# obc-v2_POWER.net
KiCad netlist of a schematic drawn in Altium Designer
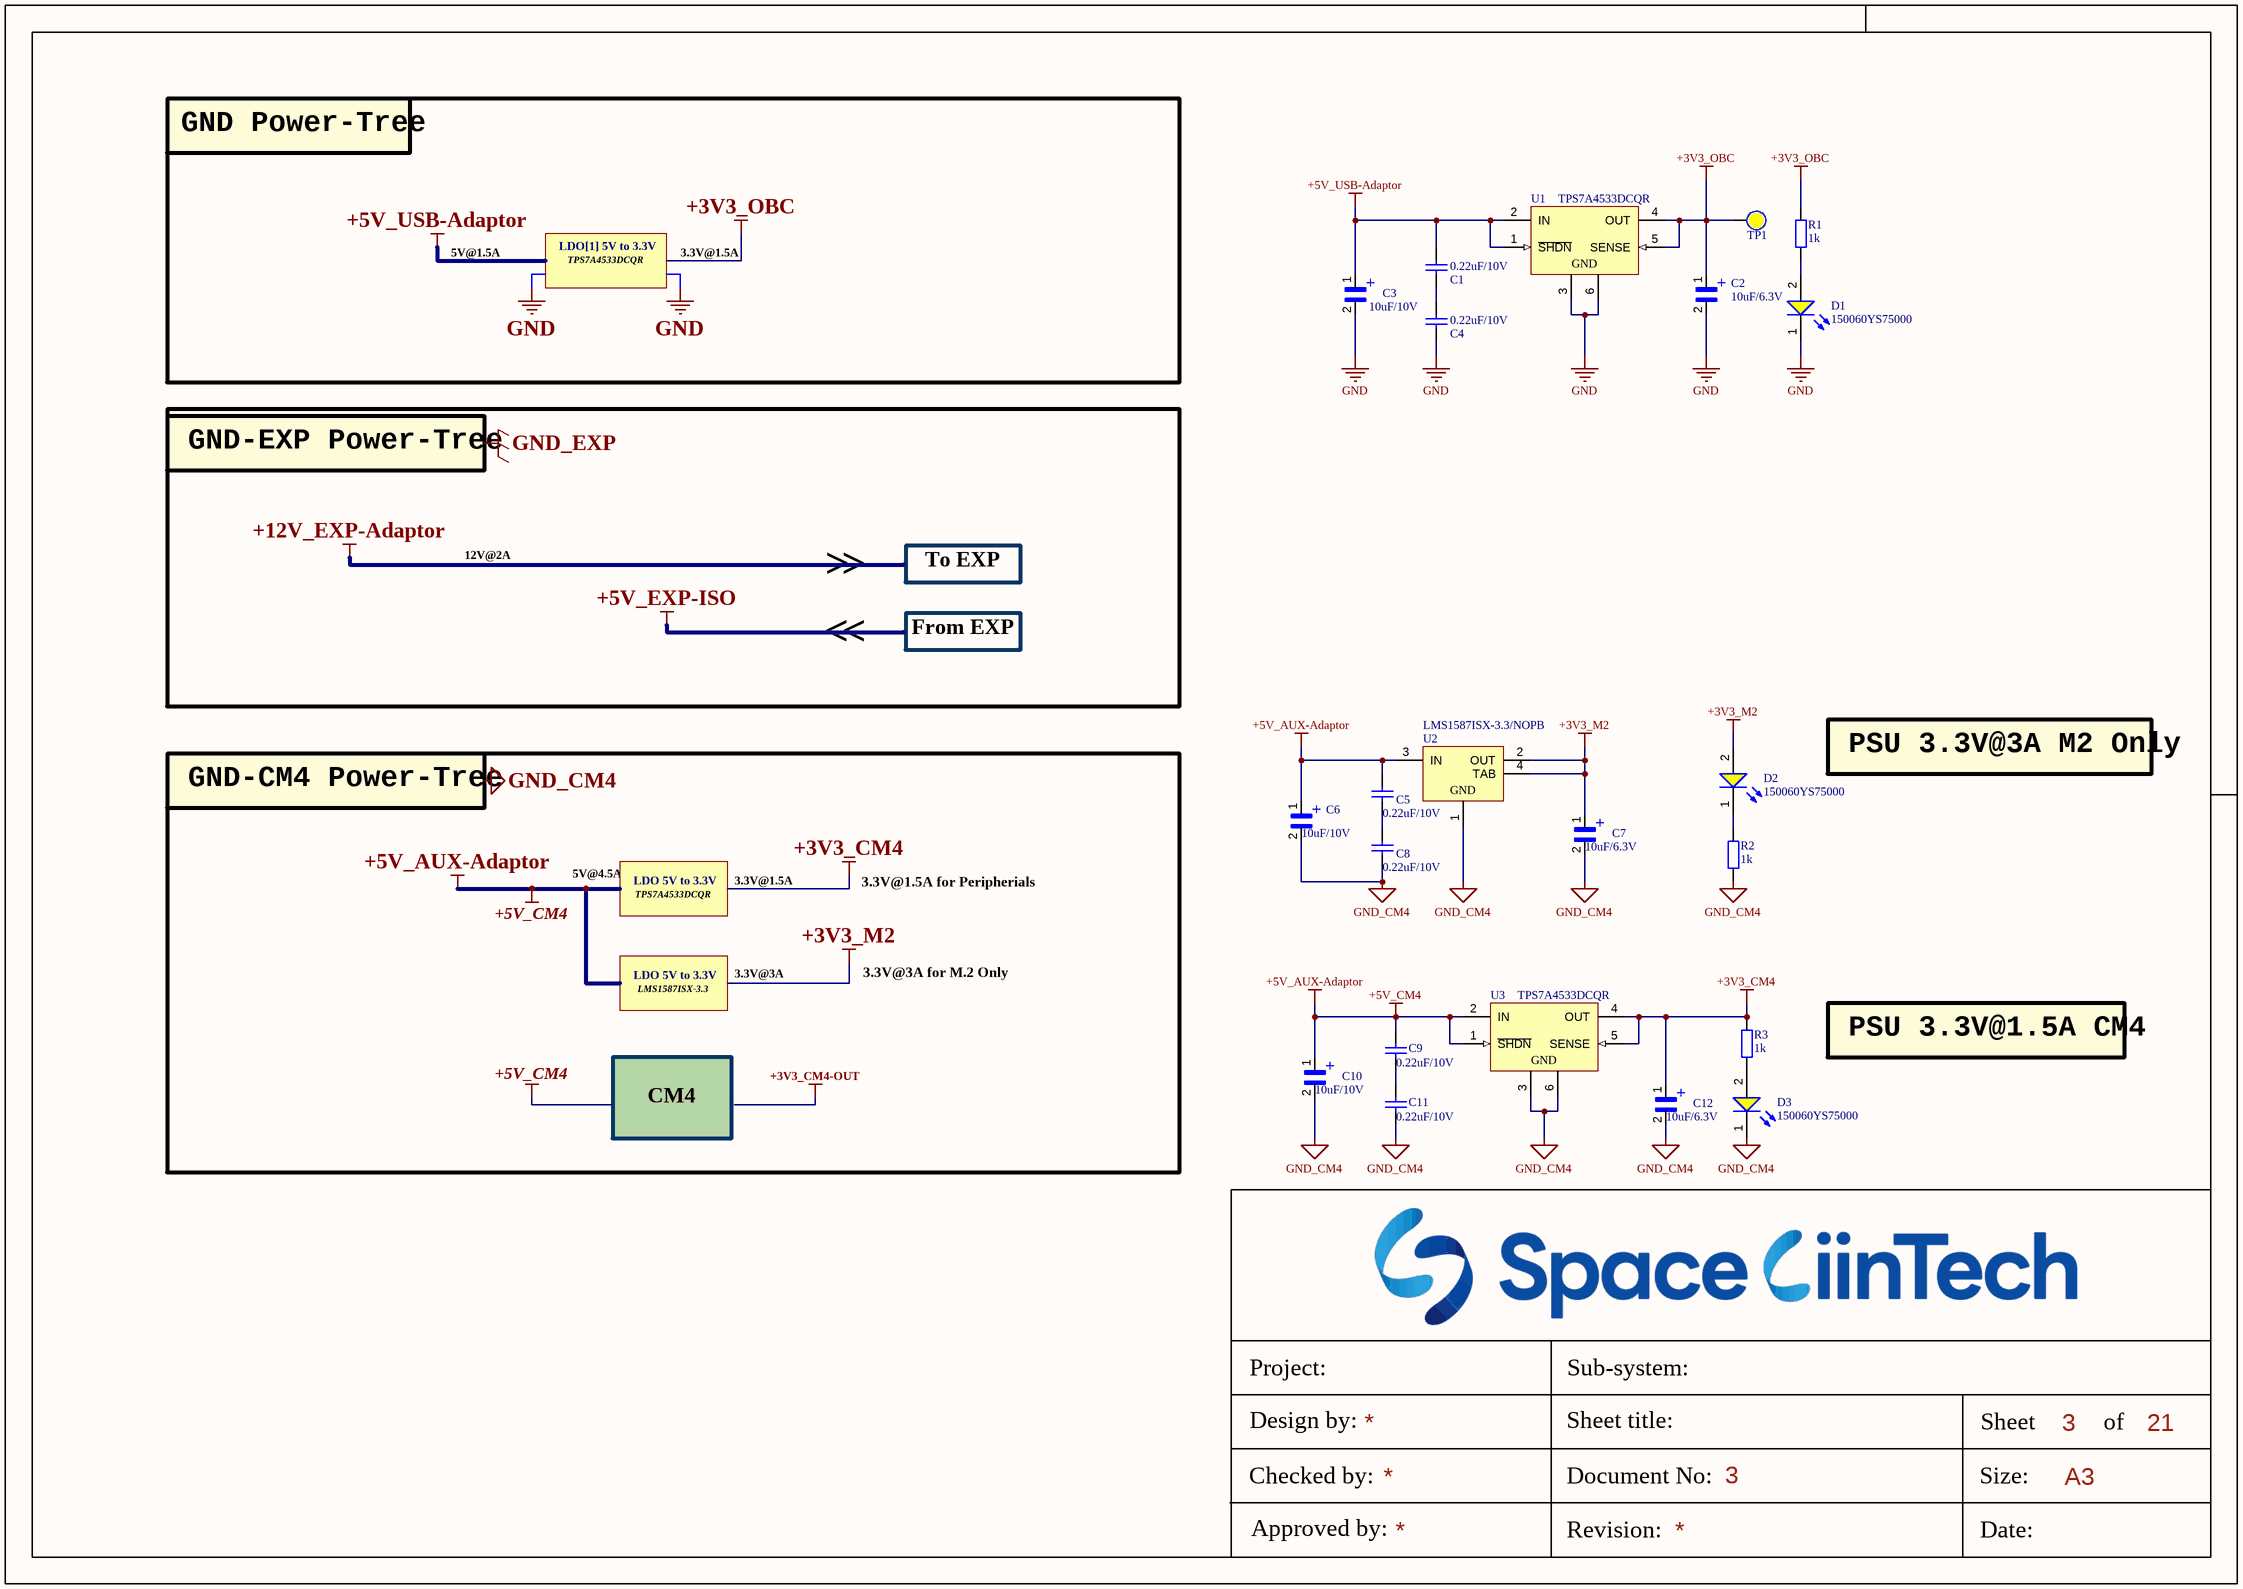
[diagram p0: obc-v2_POWER.SchDoc]

(export (version "E")
  (design (tool "Eeschema 10.0.6"))
  (components
    (comp (ref "C1")
      (value "0.22uF/10V")
      (footprint "CAP_C_1005X60")
      (description "CAPC")
      (libsource (lib "Altium_Lib_by_KhueNguyenCreator") (part "Tu 0402 33nF 10V"))
    )
    (comp (ref "C2")
      (value "10uF/6.3V")
      (footprint "CAP_MP_2012X170")
      (description "CAPP")
      (fields (field (name "MP") "TACR686M003RTA") (field (name "MF") "AVX"))
      (libsource (lib "TACR686M003RTA") (part "TACR686M003RTA"))
    )
    (comp (ref "C3")
      (value "10uF/10V")
      (footprint "CAP_MP_2012X170")
      (description "CAPP")
      (fields (field (name "MP") "TACR686M003RTA") (field (name "MF") "AVX"))
      (libsource (lib "TACR686M003RTA") (part "TACR686M003RTA"))
    )
    (comp (ref "C4")
      (value "0.22uF/10V")
      (footprint "CAP_C_1005X60")
      (description "CAPC")
      (libsource (lib "Altium_Lib_by_KhueNguyenCreator") (part "Tu 0402 33nF 10V"))
    )
    (comp (ref "C5")
      (value "0.22uF/10V")
      (footprint "CAP_C_1005X60")
      (description "CAPC")
      (libsource (lib "Altium_Lib_by_KhueNguyenCreator") (part "Tu 0402 33nF 10V"))
    )
    (comp (ref "C6")
      (value "10uF/10V")
      (footprint "CAP_MP_2012X170")
      (description "CAPP")
      (fields (field (name "MP") "TACR686M003RTA") (field (name "MF") "AVX"))
      (libsource (lib "TACR686M003RTA") (part "TACR686M003RTA"))
    )
    (comp (ref "C7")
      (value "10uF/6.3V")
      (footprint "CAP_MP_2012X170")
      (description "CAPP")
      (fields (field (name "MP") "TACR686M003RTA") (field (name "MF") "AVX"))
      (libsource (lib "TACR686M003RTA") (part "TACR686M003RTA"))
    )
    (comp (ref "C8")
      (value "0.22uF/10V")
      (footprint "CAP_C_1005X60")
      (description "CAPC")
      (libsource (lib "Altium_Lib_by_KhueNguyenCreator") (part "Tu 0402 33nF 10V"))
    )
    (comp (ref "C9")
      (value "0.22uF/10V")
      (footprint "CAP_C_1005X60")
      (description "CAPC")
      (libsource (lib "Altium_Lib_by_KhueNguyenCreator") (part "Tu 0402 33nF 10V"))
    )
    (comp (ref "C10")
      (value "10uF/10V")
      (footprint "CAP_MP_2012X170")
      (description "CAPP")
      (fields (field (name "MP") "TACR686M003RTA") (field (name "MF") "AVX"))
      (libsource (lib "TACR686M003RTA") (part "TACR686M003RTA"))
    )
    (comp (ref "C11")
      (value "0.22uF/10V")
      (footprint "CAP_C_1005X60")
      (description "CAPC")
      (libsource (lib "Altium_Lib_by_KhueNguyenCreator") (part "Tu 0402 33nF 10V"))
    )
    (comp (ref "C12")
      (value "10uF/6.3V")
      (footprint "CAP_MP_2012X170")
      (description "CAPP")
      (fields (field (name "MP") "TACR686M003RTA") (field (name "MF") "AVX"))
      (libsource (lib "TACR686M003RTA") (part "TACR686M003RTA"))
    )
    (comp (ref "D1")
      (value "150060YS75000")
      (footprint "WL-SMCW_0603_150060xx75000")
      (description "LED YELLOW CLEAR 0603 SMD")
      (libsource (lib "Altium Content Vault") (part "LED_Yellow_2A-1K"))
    )
    (comp (ref "D2")
      (value "150060YS75000")
      (footprint "WL-SMCW_0603_150060xx75000")
      (description "LED YELLOW CLEAR 0603 SMD")
      (libsource (lib "Altium Content Vault") (part "LED_Yellow_2A-1K"))
    )
    (comp (ref "D3")
      (value "150060YS75000")
      (footprint "WL-SMCW_0603_150060xx75000")
      (description "LED YELLOW CLEAR 0603 SMD")
      (libsource (lib "Altium Content Vault") (part "LED_Yellow_2A-1K"))
    )
    (comp (ref "R1")
      (value "1k")
      (footprint "RES_C_1608X60")
      (description "RES")
      (libsource (lib "Altium_Lib_by_KhueNguyenCreator") (part "Tro 0603 1% 10k"))
    )
    (comp (ref "R2")
      (value "1k")
      (footprint "RES_C_1608X60")
      (description "RES")
      (libsource (lib "Altium_Lib_by_KhueNguyenCreator") (part "Tro 0603 1% 10k"))
    )
    (comp (ref "R3")
      (value "1k")
      (footprint "RES_C_1608X60")
      (description "RES")
      (libsource (lib "Altium_Lib_by_KhueNguyenCreator") (part "Tro 0603 1% 10k"))
    )
    (comp (ref "TP1")
      (value "~")
      (footprint "Test Point 1 Side")
      (description "Test Point")
      (libsource (lib "BYTECH_HW_LIB_2019 (1)") (part "Test Point"))
    )
    (comp (ref "U1")
      (value "TPS7A4533DCQR")
      (footprint "DCQ0006A_M")
      (fields (field (name "MANUFACTURER") "Texas Instruments"))
      (libsource (lib "Altium Content Vault") (part "TI-TXXXXAXXXDCQ_KTTX"))
    )
    (comp (ref "U2")
      (value "LMS1587ISX-3.3/NOPB")
      (footprint "TS3B_L")
      (description "3A Low Dropout Fast Response Regulators, 3-pin TO-263, Pb-Free")
      (fields (field (name "MANUFACTURER") "National Semiconductor"))
      (libsource (lib "Altium Content Vault") (part "PM-REG-LM1086-SOT4"))
    )
    (comp (ref "U3")
      (value "TPS7A4533DCQR")
      (footprint "DCQ0006A_M")
      (fields (field (name "MANUFACTURER") "Texas Instruments"))
      (libsource (lib "Altium Content Vault") (part "TI-TXXXXAXXXDCQ_KTTX"))
    )
  )
  (nets
    (net (code "1") (name "+3V3_CM4") (class "Default")
      (node (ref "C12") (pin "1") (pinfunction "1_1") (pintype "passive"))
      (node (ref "R3") (pin "2") (pinfunction "2_2") (pintype "passive"))
      (node (ref "U3") (pin "4") (pinfunction "OUT_4") (pintype "power_in"))
      (node (ref "U3") (pin "5") (pinfunction "SENSE_5") (pintype "input"))
    )
    (net (code "3") (name "+3V3_M2") (class "Default")
      (node (ref "C7") (pin "1") (pinfunction "1_1") (pintype "passive"))
      (node (ref "D2") (pin "2") (pinfunction "A_2") (pintype "passive"))
      (node (ref "U2") (pin "2") (pinfunction "OUT_2") (pintype "power_in"))
      (node (ref "U2") (pin "4") (pinfunction "TAB_4") (pintype "power_in"))
    )
    (net (code "4") (name "+3V3_OBC") (class "Default")
      (node (ref "C2") (pin "1") (pinfunction "1_1") (pintype "passive"))
      (node (ref "R1") (pin "2") (pinfunction "2_2") (pintype "passive"))
      (node (ref "TP1") (pin "0") (pinfunction "0_0") (pintype "passive"))
      (node (ref "U1") (pin "4") (pinfunction "OUT_4") (pintype "power_in"))
      (node (ref "U1") (pin "5") (pinfunction "SENSE_5") (pintype "input"))
    )
    (net (code "5") (name "+5V_AUX-Adaptor") (class "Default")
      (node (ref "C10") (pin "1") (pinfunction "1_1") (pintype "passive"))
      (node (ref "C5") (pin "1") (pinfunction "1_1") (pintype "passive"))
      (node (ref "C6") (pin "1") (pinfunction "1_1") (pintype "passive"))
      (node (ref "C9") (pin "1") (pinfunction "1_1") (pintype "passive"))
      (node (ref "U2") (pin "3") (pinfunction "IN_3") (pintype "power_in"))
      (node (ref "U3") (pin "1") (pinfunction "~{SHDN}_1") (pintype "input"))
      (node (ref "U3") (pin "2") (pinfunction "IN_2") (pintype "power_in"))
    )
    (net (code "7") (name "+5V_USB-Adaptor") (class "Default")
      (node (ref "C1") (pin "1") (pinfunction "1_1") (pintype "passive"))
      (node (ref "C3") (pin "1") (pinfunction "1_1") (pintype "passive"))
      (node (ref "U1") (pin "1") (pinfunction "~{SHDN}_1") (pintype "input"))
      (node (ref "U1") (pin "2") (pinfunction "IN_2") (pintype "power_in"))
    )
    (net (code "9") (name "GND") (class "Default")
      (node (ref "C2") (pin "2") (pinfunction "2_2") (pintype "passive"))
      (node (ref "C3") (pin "2") (pinfunction "2_2") (pintype "passive"))
      (node (ref "C4") (pin "2") (pinfunction "2_2") (pintype "passive"))
      (node (ref "D1") (pin "1") (pinfunction "K_1") (pintype "passive"))
      (node (ref "U1") (pin "3") (pinfunction "GND_3") (pintype "power_in"))
      (node (ref "U1") (pin "6") (pinfunction "GND_6") (pintype "power_in"))
    )
    (net (code "10") (name "GND_CM4") (class "Default")
      (node (ref "C10") (pin "2") (pinfunction "2_2") (pintype "passive"))
      (node (ref "C11") (pin "2") (pinfunction "2_2") (pintype "passive"))
      (node (ref "C12") (pin "2") (pinfunction "2_2") (pintype "passive"))
      (node (ref "C6") (pin "2") (pinfunction "2_2") (pintype "passive"))
      (node (ref "C7") (pin "2") (pinfunction "2_2") (pintype "passive"))
      (node (ref "C8") (pin "2") (pinfunction "2_2") (pintype "passive"))
      (node (ref "D3") (pin "1") (pinfunction "K_1") (pintype "passive"))
      (node (ref "R2") (pin "2") (pinfunction "2_2") (pintype "passive"))
      (node (ref "U2") (pin "1") (pinfunction "GND_1") (pintype "power_in"))
      (node (ref "U3") (pin "3") (pinfunction "GND_3") (pintype "power_in"))
      (node (ref "U3") (pin "6") (pinfunction "GND_6") (pintype "power_in"))
    )
    (net (code "12") (name "Net-(C1-Pad2)") (class "Default")
      (node (ref "C1") (pin "2") (pinfunction "2_2") (pintype "passive"))
      (node (ref "C4") (pin "1") (pinfunction "1_1") (pintype "passive"))
    )
    (net (code "13") (name "Net-(C5-Pad2)") (class "Default")
      (node (ref "C5") (pin "2") (pinfunction "2_2") (pintype "passive"))
      (node (ref "C8") (pin "1") (pinfunction "1_1") (pintype "passive"))
    )
    (net (code "14") (name "Net-(C11-Pad1)") (class "Default")
      (node (ref "C11") (pin "1") (pinfunction "1_1") (pintype "passive"))
      (node (ref "C9") (pin "2") (pinfunction "2_2") (pintype "passive"))
    )
    (net (code "15") (name "Net-(D1-A)") (class "Default")
      (node (ref "D1") (pin "2") (pinfunction "A_2") (pintype "passive"))
      (node (ref "R1") (pin "1") (pinfunction "1_1") (pintype "passive"))
    )
    (net (code "16") (name "Net-(D2-K)") (class "Default")
      (node (ref "D2") (pin "1") (pinfunction "K_1") (pintype "passive"))
      (node (ref "R2") (pin "1") (pinfunction "1_1") (pintype "passive"))
    )
    (net (code "17") (name "Net-(D3-A)") (class "Default")
      (node (ref "D3") (pin "2") (pinfunction "A_2") (pintype "passive"))
      (node (ref "R3") (pin "1") (pinfunction "1_1") (pintype "passive"))
    )
  )
)
